# blds.net
KiCad netlist of a schematic drawn in Altium Designer
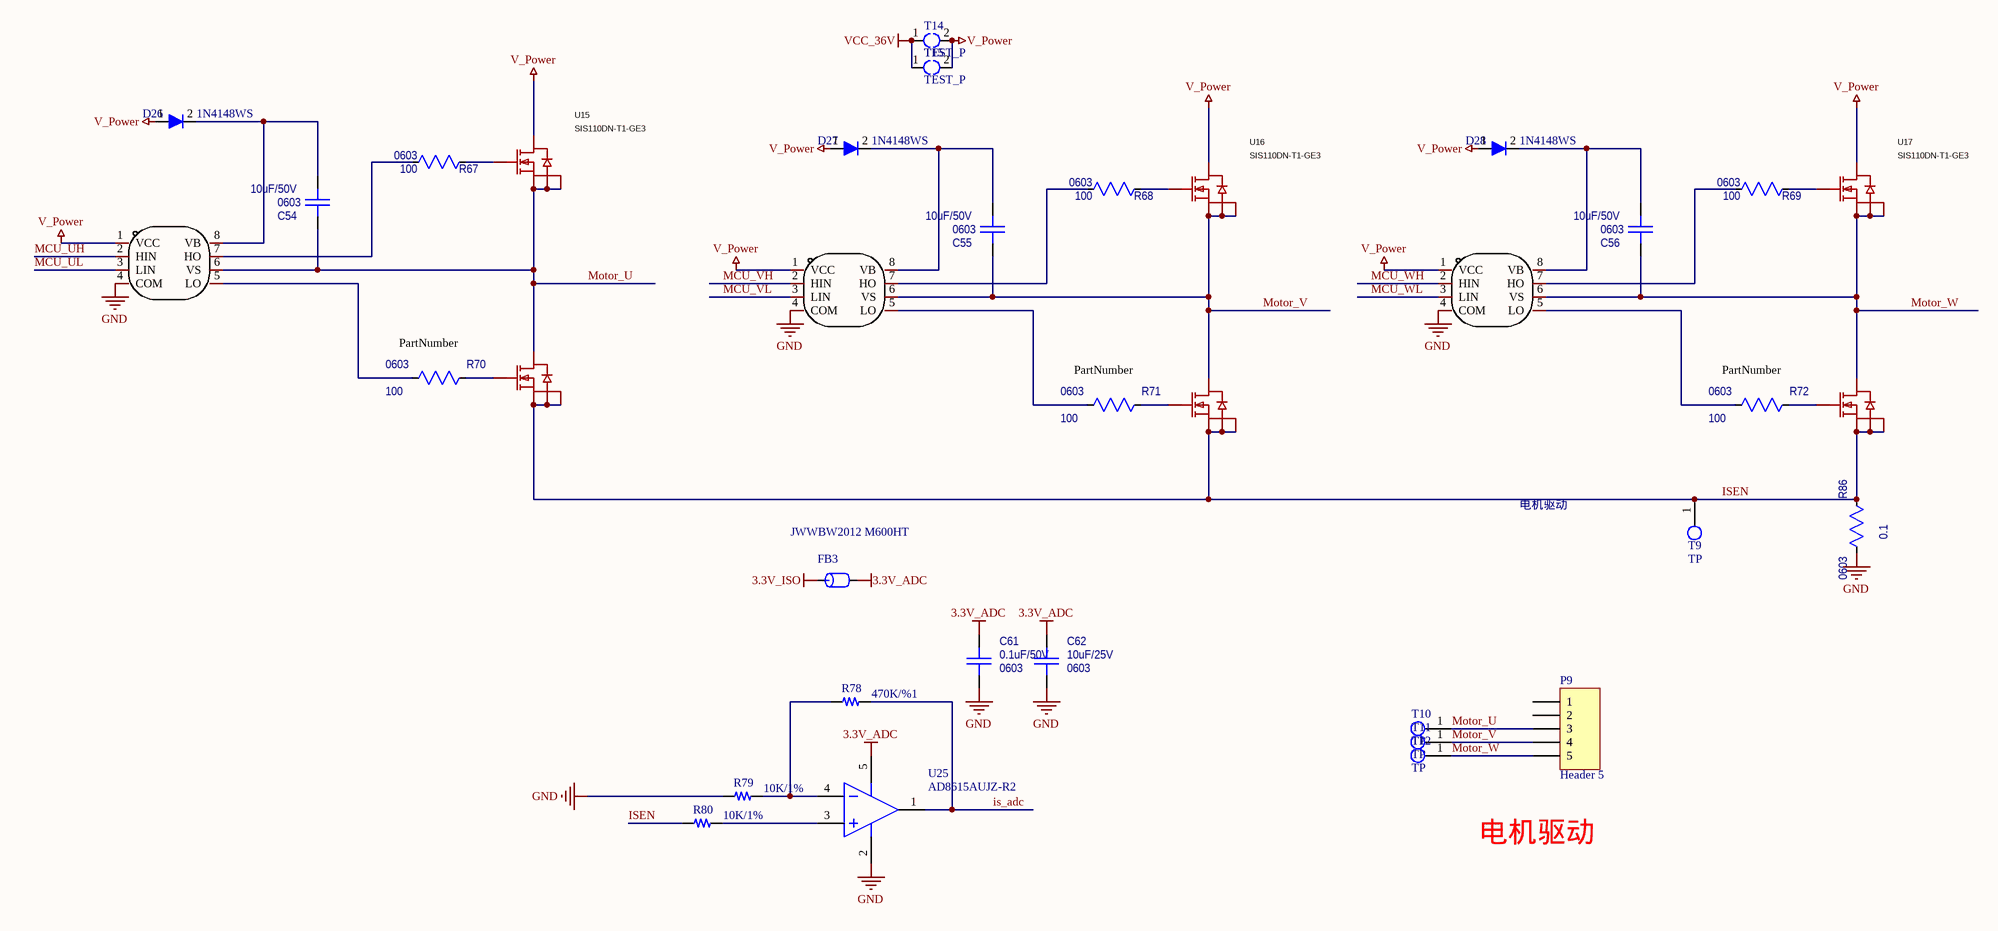
[diagram p0: blds.SchDoc]

(export (version "E")
  (design (tool "Eeschema 10.0.6"))
  (components
    (comp (ref "C54")
      (value "10uF/50V")
      (footprint "CAPC1608X092N_0603")
      (description "Capacitor, MLCC")
      (fields
        (field (name "MANUFACTURER") "muRata")
        (field (name "PARTNUMBER") "GQM2195C2E4R7CB12J")
        (field (name "PACKAGE") "0603")
      )
      (libsource (lib "Karl") (part "Capacitor_0603"))
    )
    (comp (ref "C55")
      (value "10uF/50V")
      (footprint "CAPC1608X092N_0603")
      (description "Capacitor, MLCC")
      (fields
        (field (name "MANUFACTURER") "muRata")
        (field (name "PARTNUMBER") "GQM2195C2E4R7CB12J")
        (field (name "PACKAGE") "0603")
      )
      (libsource (lib "Karl") (part "Capacitor_0603"))
    )
    (comp (ref "C56")
      (value "10uF/50V")
      (footprint "CAPC1608X092N_0603")
      (description "Capacitor, MLCC")
      (fields
        (field (name "MANUFACTURER") "muRata")
        (field (name "PARTNUMBER") "GQM2195C2E4R7CB12J")
        (field (name "PACKAGE") "0603")
      )
      (libsource (lib "Karl") (part "Capacitor_0603"))
    )
    (comp (ref "C61")
      (value "0.1uF/50V")
      (footprint "CAPC1608X092N_0603")
      (fields
        (field (name "PARTNUMBER") "C0603C104M5RACTU")
        (field (name "TOLERANCE") "[tol]")
        (field (name "PACKAGE") "0603")
        (field (name "Comment") "Capacitor_0603")
      )
      (libsource (lib "Karl") (part "Capacitor_0603"))
    )
    (comp (ref "C62")
      (value "10uF/25V")
      (footprint "CAPC1608X092N_0603")
      (fields
        (field (name "PARTNUMBER") "C0603C104M5RACTU")
        (field (name "TOLERANCE") "[tol]")
        (field (name "PACKAGE") "0603")
        (field (name "Comment") "Capacitor_0603")
      )
      (libsource (lib "Karl") (part "Capacitor_0603"))
    )
    (comp (ref "D26") (value "1N4148WS") (footprint "SOD323") (libsource (lib "Device2018") (part "LL4148")))
    (comp (ref "D27") (value "1N4148WS") (footprint "SOD323") (libsource (lib "Device2018") (part "LL4148")))
    (comp (ref "D28") (value "1N4148WS") (footprint "SOD323") (libsource (lib "Device2018") (part "LL4148")))
    (comp (ref "FB3")
      (value "JWWBW2012 M600HT")
      (footprint "0805R")
      (libsource (lib "Schlib_20110825") (part "FB"))
    )
    (comp (ref "P9")
      (value "Header 5")
      (footprint "HDR1X5")
      (description "Header, 5-Pin")
      (fields (field (name "PUBLISHER") "Altium Limited"))
      (libsource (lib "Miscellaneous Connectors") (part "Header 5"))
    )
    (comp (ref "R67")
      (value "100")
      (footprint "RESC1608X055N_0603")
      (description "Resistor, Standard")
      (fields
        (field (name "MANUFACTURER") "Yageo")
        (field (name "PARTNUMBER") "RC0603FR-0710KL")
        (field (name "PACKAGE") "0603")
      )
      (libsource (lib "Karl") (part "Resistor_0603"))
    )
    (comp (ref "R68")
      (value "100")
      (footprint "RESC1608X055N_0603")
      (description "Resistor, Standard")
      (fields
        (field (name "MANUFACTURER") "Yageo")
        (field (name "PARTNUMBER") "RC0603FR-0710KL")
        (field (name "PACKAGE") "0603")
      )
      (libsource (lib "Karl") (part "Resistor_0603"))
    )
    (comp (ref "R69")
      (value "100")
      (footprint "RESC1608X055N_0603")
      (description "Resistor, Standard")
      (fields
        (field (name "MANUFACTURER") "Yageo")
        (field (name "PARTNUMBER") "RC0603FR-0710KL")
        (field (name "PACKAGE") "0603")
      )
      (libsource (lib "Karl") (part "Resistor_0603"))
    )
    (comp (ref "R70")
      (value "100")
      (footprint "RESC1608X055N_0603")
      (description "Resistor, Standard")
      (fields
        (field (name "MANUFACTURER") "Yageo")
        (field (name "PARTNUMBER") "RC0603FR-0710KL")
        (field (name "PACKAGE") "0603")
      )
      (libsource (lib "Karl") (part "Resistor_0603"))
    )
    (comp (ref "R71")
      (value "100")
      (footprint "RESC1608X055N_0603")
      (description "Resistor, Standard")
      (fields
        (field (name "MANUFACTURER") "Yageo")
        (field (name "PARTNUMBER") "RC0603FR-0710KL")
        (field (name "PACKAGE") "0603")
      )
      (libsource (lib "Karl") (part "Resistor_0603"))
    )
    (comp (ref "R72")
      (value "100")
      (footprint "RESC1608X055N_0603")
      (description "Resistor, Standard")
      (fields
        (field (name "MANUFACTURER") "Yageo")
        (field (name "PARTNUMBER") "RC0603FR-0710KL")
        (field (name "PACKAGE") "0603")
      )
      (libsource (lib "Karl") (part "Resistor_0603"))
    )
    (comp (ref "R78") (value "470K/%1") (footprint "0603R") (libsource (lib "JRJ_1") (part "R")))
    (comp (ref "R79") (value "10K/1%") (footprint "0603R") (libsource (lib "JRJ_1") (part "R")))
    (comp (ref "R80") (value "10K/1%") (footprint "0603R") (libsource (lib "JRJ_1") (part "R")))
    (comp (ref "R86")
      (value "0.1")
      (footprint "2010R")
      (description "Resistor, Standard")
      (fields
        (field (name "MANUFACTURER") "Yageo")
        (field (name "PARTNUMBER") "RC0603FR-0710KL")
        (field (name "PACKAGE") "0603")
      )
      (libsource (lib "Karl") (part "Resistor_0603"))
    )
    (comp (ref "T9") (value "TP") (footprint "TPD") (libsource (lib "Schlib_20110825") (part "TP")))
    (comp (ref "T10") (value "TP") (footprint "TPD") (libsource (lib "Schlib_20110825") (part "TP")))
    (comp (ref "T11") (value "TP") (footprint "TPD") (libsource (lib "Schlib_20110825") (part "TP")))
    (comp (ref "T12") (value "TP") (footprint "TPD") (libsource (lib "Schlib_20110825") (part "TP")))
    (comp (ref "T14")
      (value "TEST_P")
      (footprint "TEST_P")
      (libsource (lib "Schlib_20110825") (part "TEST_P"))
    )
    (comp (ref "T15")
      (value "TEST_P")
      (footprint "TEST_P")
      (libsource (lib "Schlib_20110825") (part "TEST_P"))
    )
    (comp (ref "U15")
      (value "SIS110DN-T1-GE3")
      (footprint "DFN-8_L3.3-W3.3-P0.65-BL-2")
      (fields (field (name "MANUFACTURER") "VISHAY(威世)"))
      (libsource (lib "altium-import") (part "root_0_SIS110DN-T1-GE3_"))
    )
    (comp (ref "U16")
      (value "SIS110DN-T1-GE3")
      (footprint "DFN-8_L3.3-W3.3-P0.65-BL-2")
      (fields (field (name "MANUFACTURER") "VISHAY(威世)"))
      (libsource (lib "altium-import") (part "root_0_SIS110DN-T1-GE3_"))
    )
    (comp (ref "U17")
      (value "SIS110DN-T1-GE3")
      (footprint "DFN-8_L3.3-W3.3-P0.65-BL-2")
      (fields (field (name "MANUFACTURER") "VISHAY(威世)"))
      (libsource (lib "altium-import") (part "root_0_SIS110DN-T1-GE3_"))
    )
    (comp (ref "U18")
      (value "IRS21867STRPBF")
      (footprint "SO-8")
      (fields (field (name "MANUFACTURER") "Infineon(英飞凌)"))
      (libsource (lib "altium-import") (part "root_0_IRS21867STRPBF_"))
    )
    (comp (ref "U19")
      (value "IRS21867STRPBF")
      (footprint "SO-8")
      (fields (field (name "MANUFACTURER") "Infineon(英飞凌)"))
      (libsource (lib "altium-import") (part "root_0_IRS21867STRPBF_"))
    )
    (comp (ref "U20")
      (value "IRS21867STRPBF")
      (footprint "SO-8")
      (fields (field (name "MANUFACTURER") "Infineon(英飞凌)"))
      (libsource (lib "altium-import") (part "root_0_IRS21867STRPBF_"))
    )
    (comp (ref "U21")
      (value "SIS110DN-T1-GE3")
      (footprint "DFN-8_L3.3-W3.3-P0.65-BL-2")
      (fields (field (name "MANUFACTURER") "VISHAY(威世)"))
      (libsource (lib "altium-import") (part "root_0_SIS110DN-T1-GE3_"))
    )
    (comp (ref "U22")
      (value "SIS110DN-T1-GE3")
      (footprint "DFN-8_L3.3-W3.3-P0.65-BL-2")
      (fields (field (name "MANUFACTURER") "VISHAY(威世)"))
      (libsource (lib "altium-import") (part "root_0_SIS110DN-T1-GE3_"))
    )
    (comp (ref "U23")
      (value "SIS110DN-T1-GE3")
      (footprint "DFN-8_L3.3-W3.3-P0.65-BL-2")
      (fields (field (name "MANUFACTURER") "VISHAY(威世)"))
      (libsource (lib "altium-import") (part "root_0_SIS110DN-T1-GE3_"))
    )
    (comp (ref "U25")
      (value "AD8615AUJZ-R2")
      (footprint "sot-23-5")
      (libsource (lib "Schlib_20110825") (part "AD8615"))
    )
  )
  (nets
    (net (code "1") (name "/ISEN") (class "Default")
      (node (ref "R80") (pin "2") (pintype "passive"))
      (node (ref "R86") (pin "2") (pinfunction "2_2") (pintype "passive"))
      (node (ref "T9") (pin "1") (pintype "passive"))
      (node (ref "U21") (pin "1") (pinfunction "S_1") (pintype "passive"))
      (node (ref "U21") (pin "2") (pinfunction "S_2") (pintype "passive"))
      (node (ref "U21") (pin "3") (pinfunction "S_3") (pintype "passive"))
      (node (ref "U22") (pin "1") (pinfunction "S_1") (pintype "passive"))
      (node (ref "U22") (pin "2") (pinfunction "S_2") (pintype "passive"))
      (node (ref "U22") (pin "3") (pinfunction "S_3") (pintype "passive"))
      (node (ref "U23") (pin "1") (pinfunction "S_1") (pintype "passive"))
      (node (ref "U23") (pin "2") (pinfunction "S_2") (pintype "passive"))
      (node (ref "U23") (pin "3") (pinfunction "S_3") (pintype "passive"))
    )
    (net (code "2") (name "/MCU_UH") (class "Default")
      (node (ref "U18") (pin "2") (pinfunction "HIN_2") (pintype "passive"))
    )
    (net (code "3") (name "/MCU_UL") (class "Default")
      (node (ref "U18") (pin "3") (pinfunction "LIN_3") (pintype "passive"))
    )
    (net (code "4") (name "/MCU_VH") (class "Default")
      (node (ref "U19") (pin "2") (pinfunction "HIN_2") (pintype "passive"))
    )
    (net (code "5") (name "/MCU_VL") (class "Default")
      (node (ref "U19") (pin "3") (pinfunction "LIN_3") (pintype "passive"))
    )
    (net (code "6") (name "/MCU_WH") (class "Default")
      (node (ref "U20") (pin "2") (pinfunction "HIN_2") (pintype "passive"))
    )
    (net (code "7") (name "/MCU_WL") (class "Default")
      (node (ref "U20") (pin "3") (pinfunction "LIN_3") (pintype "passive"))
    )
    (net (code "8") (name "/Motor_U") (class "Default")
      (node (ref "C54") (pin "1") (pinfunction "1_1") (pintype "passive"))
      (node (ref "P9") (pin "3") (pinfunction "3_3") (pintype "passive"))
      (node (ref "T10") (pin "1") (pintype "passive"))
      (node (ref "U15") (pin "1") (pinfunction "S_1") (pintype "passive"))
      (node (ref "U15") (pin "2") (pinfunction "S_2") (pintype "passive"))
      (node (ref "U15") (pin "3") (pinfunction "S_3") (pintype "passive"))
      (node (ref "U18") (pin "6") (pinfunction "VS_6") (pintype "passive"))
      (node (ref "U21") (pin "5") (pinfunction "D_5") (pintype "passive"))
    )
    (net (code "9") (name "/Motor_V") (class "Default")
      (node (ref "C55") (pin "1") (pinfunction "1_1") (pintype "passive"))
      (node (ref "P9") (pin "4") (pinfunction "4_4") (pintype "passive"))
      (node (ref "T11") (pin "1") (pintype "passive"))
      (node (ref "U16") (pin "1") (pinfunction "S_1") (pintype "passive"))
      (node (ref "U16") (pin "2") (pinfunction "S_2") (pintype "passive"))
      (node (ref "U16") (pin "3") (pinfunction "S_3") (pintype "passive"))
      (node (ref "U19") (pin "6") (pinfunction "VS_6") (pintype "passive"))
      (node (ref "U22") (pin "5") (pinfunction "D_5") (pintype "passive"))
    )
    (net (code "10") (name "/Motor_W") (class "Default")
      (node (ref "C56") (pin "1") (pinfunction "1_1") (pintype "passive"))
      (node (ref "P9") (pin "5") (pinfunction "5_5") (pintype "passive"))
      (node (ref "T12") (pin "1") (pintype "passive"))
      (node (ref "U17") (pin "1") (pinfunction "S_1") (pintype "passive"))
      (node (ref "U17") (pin "2") (pinfunction "S_2") (pintype "passive"))
      (node (ref "U17") (pin "3") (pinfunction "S_3") (pintype "passive"))
      (node (ref "U20") (pin "6") (pinfunction "VS_6") (pintype "passive"))
      (node (ref "U23") (pin "5") (pinfunction "D_5") (pintype "passive"))
    )
    (net (code "11") (name "/is_adc") (class "Default")
      (node (ref "R78") (pin "1") (pintype "passive"))
      (node (ref "U25") (pin "1") (pinfunction "OS_NUL_1") (pintype "passive"))
    )
    (net (code "12") (name "3.3V_ADC") (class "Default")
      (node (ref "C61") (pin "1") (pinfunction "1_1") (pintype "passive"))
      (node (ref "C62") (pin "1") (pinfunction "1_1") (pintype "passive"))
      (node (ref "FB3") (pin "2") (pintype "passive"))
      (node (ref "U25") (pin "5") (pinfunction "VCC_5") (pintype "passive"))
    )
    (net (code "13") (name "3.3V_ISO") (class "Default") (node (ref "FB3") (pin "1") (pintype "passive")))
    (net (code "14") (name "GND") (class "Default")
      (node (ref "C61") (pin "2") (pinfunction "2_2") (pintype "passive"))
      (node (ref "C62") (pin "2") (pinfunction "2_2") (pintype "passive"))
      (node (ref "R79") (pin "2") (pintype "passive"))
      (node (ref "R86") (pin "1") (pinfunction "1_1") (pintype "passive"))
      (node (ref "U18") (pin "4") (pinfunction "COM_4") (pintype "passive"))
      (node (ref "U19") (pin "4") (pinfunction "COM_4") (pintype "passive"))
      (node (ref "U20") (pin "4") (pinfunction "COM_4") (pintype "passive"))
      (node (ref "U25") (pin "2") (pinfunction "G_2") (pintype "power_in"))
    )
    (net (code "15") (name "Net-(D26-A)") (class "Default")
      (node (ref "C54") (pin "2") (pinfunction "2_2") (pintype "passive"))
      (node (ref "D26") (pin "2") (pinfunction "A_2") (pintype "passive"))
      (node (ref "U18") (pin "8") (pinfunction "VB_8") (pintype "passive"))
    )
    (net (code "16") (name "Net-(D27-A)") (class "Default")
      (node (ref "C55") (pin "2") (pinfunction "2_2") (pintype "passive"))
      (node (ref "D27") (pin "2") (pinfunction "A_2") (pintype "passive"))
      (node (ref "U19") (pin "8") (pinfunction "VB_8") (pintype "passive"))
    )
    (net (code "17") (name "Net-(D28-A)") (class "Default")
      (node (ref "C56") (pin "2") (pinfunction "2_2") (pintype "passive"))
      (node (ref "D28") (pin "2") (pinfunction "A_2") (pintype "passive"))
      (node (ref "U20") (pin "8") (pinfunction "VB_8") (pintype "passive"))
    )
    (net (code "18") (name "Net-(U15-G)") (class "Default")
      (node (ref "R67") (pin "2") (pinfunction "2_2") (pintype "passive"))
      (node (ref "U15") (pin "4") (pinfunction "G_4") (pintype "passive"))
    )
    (net (code "19") (name "Net-(U16-G)") (class "Default")
      (node (ref "R68") (pin "2") (pinfunction "2_2") (pintype "passive"))
      (node (ref "U16") (pin "4") (pinfunction "G_4") (pintype "passive"))
    )
    (net (code "20") (name "Net-(U17-G)") (class "Default")
      (node (ref "R69") (pin "2") (pinfunction "2_2") (pintype "passive"))
      (node (ref "U17") (pin "4") (pinfunction "G_4") (pintype "passive"))
    )
    (net (code "21") (name "Net-(U18-HO)") (class "Default")
      (node (ref "R67") (pin "1") (pinfunction "1_1") (pintype "passive"))
      (node (ref "U18") (pin "7") (pinfunction "HO_7") (pintype "passive"))
    )
    (net (code "22") (name "Net-(U18-LO)") (class "Default")
      (node (ref "R70") (pin "1") (pinfunction "1_1") (pintype "passive"))
      (node (ref "U18") (pin "5") (pinfunction "LO_5") (pintype "passive"))
    )
    (net (code "23") (name "Net-(U19-HO)") (class "Default")
      (node (ref "R68") (pin "1") (pinfunction "1_1") (pintype "passive"))
      (node (ref "U19") (pin "7") (pinfunction "HO_7") (pintype "passive"))
    )
    (net (code "24") (name "Net-(U19-LO)") (class "Default")
      (node (ref "R71") (pin "1") (pinfunction "1_1") (pintype "passive"))
      (node (ref "U19") (pin "5") (pinfunction "LO_5") (pintype "passive"))
    )
    (net (code "25") (name "Net-(U20-HO)") (class "Default")
      (node (ref "R69") (pin "1") (pinfunction "1_1") (pintype "passive"))
      (node (ref "U20") (pin "7") (pinfunction "HO_7") (pintype "passive"))
    )
    (net (code "26") (name "Net-(U20-LO)") (class "Default")
      (node (ref "R72") (pin "1") (pinfunction "1_1") (pintype "passive"))
      (node (ref "U20") (pin "5") (pinfunction "LO_5") (pintype "passive"))
    )
    (net (code "27") (name "Net-(U21-G)") (class "Default")
      (node (ref "R70") (pin "2") (pinfunction "2_2") (pintype "passive"))
      (node (ref "U21") (pin "4") (pinfunction "G_4") (pintype "passive"))
    )
    (net (code "28") (name "Net-(U22-G)") (class "Default")
      (node (ref "R71") (pin "2") (pinfunction "2_2") (pintype "passive"))
      (node (ref "U22") (pin "4") (pinfunction "G_4") (pintype "passive"))
    )
    (net (code "29") (name "Net-(U23-G)") (class "Default")
      (node (ref "R72") (pin "2") (pinfunction "2_2") (pintype "passive"))
      (node (ref "U23") (pin "4") (pinfunction "G_4") (pintype "passive"))
    )
    (net (code "30") (name "Net-(U25-V+)") (class "Default")
      (node (ref "R80") (pin "1") (pintype "passive"))
      (node (ref "U25") (pin "3") (pinfunction "V+_3") (pintype "power_in"))
    )
    (net (code "31") (name "Net-(U25-V-)") (class "Default")
      (node (ref "R78") (pin "2") (pintype "passive"))
      (node (ref "R79") (pin "1") (pintype "passive"))
      (node (ref "U25") (pin "4") (pinfunction "V-_4") (pintype "power_in"))
    )
    (net (code "32") (name "VCC_36V") (class "Default")
      (node (ref "T14") (pin "1") (pinfunction "1_1") (pintype "passive"))
      (node (ref "T15") (pin "1") (pinfunction "1_1") (pintype "passive"))
    )
    (net (code "33") (name "V_Power") (class "Default")
      (node (ref "D26") (pin "1") (pinfunction "K_1") (pintype "passive"))
      (node (ref "D27") (pin "1") (pinfunction "K_1") (pintype "passive"))
      (node (ref "D28") (pin "1") (pinfunction "K_1") (pintype "passive"))
      (node (ref "T14") (pin "2") (pinfunction "2_2") (pintype "passive"))
      (node (ref "T15") (pin "2") (pinfunction "2_2") (pintype "passive"))
      (node (ref "U15") (pin "5") (pinfunction "D_5") (pintype "passive"))
      (node (ref "U16") (pin "5") (pinfunction "D_5") (pintype "passive"))
      (node (ref "U17") (pin "5") (pinfunction "D_5") (pintype "passive"))
      (node (ref "U18") (pin "1") (pinfunction "VCC_1") (pintype "passive"))
      (node (ref "U19") (pin "1") (pinfunction "VCC_1") (pintype "passive"))
      (node (ref "U20") (pin "1") (pinfunction "VCC_1") (pintype "passive"))
    )
    (net (code "34") (name "unconnected-(P9-Pad1)") (class "Default")
      (node (ref "P9") (pin "1") (pinfunction "1_1") (pintype "passive"))
    )
    (net (code "35") (name "unconnected-(P9-Pad2)") (class "Default")
      (node (ref "P9") (pin "2") (pinfunction "2_2") (pintype "passive"))
    )
  )
)
